# ESP-WRITE.net
KiCad netlist of a schematic drawn in EAGLE
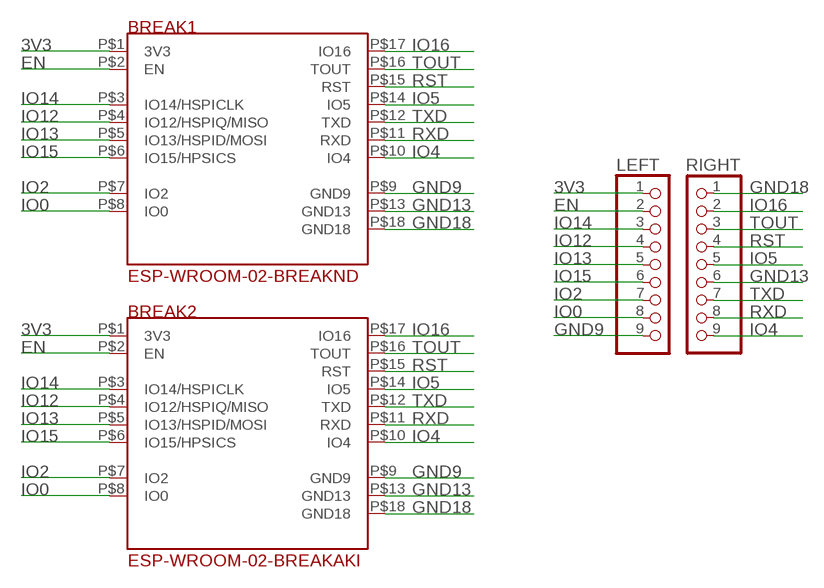
[diagram p0: schematic, sheet 1]

(export (version "E")
  (design (tool "Eeschema 10.0.6"))
  (components
    (comp (ref "BREAK1")
      (value "ESP-WROOM-02-BREAKND")
      (footprint "eagle-import:ESP-WROOM-02-BREAK-NODETAIL")
      (libsource (lib "eagle-import") (part "ESP-WROOM-02-BREAKND"))
    )
    (comp (ref "BREAK2")
      (value "ESP-WROOM-02-BREAKAKI")
      (footprint "eagle-import:ESP-WROOM-02-AKI")
      (libsource (lib "eagle-import") (part "ESP-WROOM-02-BREAKAKI"))
    )
    (comp (ref "LEFT")
      (value "PINHD-1X9")
      (footprint "eagle-import:1X09")
      (libsource (lib "eagle-import") (part "PINHD-1X9"))
    )
    (comp (ref "RIGHT")
      (value "PINHD-1X9")
      (footprint "eagle-import:1X09")
      (libsource (lib "eagle-import") (part "PINHD-1X9"))
    )
  )
  (nets
    (net (code "1") (name "/3V3") (class "Default")
      (node (ref "BREAK1") (pin "P$1") (pinfunction "3V3_P$1") (pintype "bidirectional"))
      (node (ref "BREAK2") (pin "P$1") (pinfunction "3V3_P$1") (pintype "bidirectional"))
      (node (ref "LEFT") (pin "1") (pinfunction "1_1") (pintype "passive"))
    )
    (net (code "2") (name "/EN") (class "Default")
      (node (ref "BREAK1") (pin "P$2") (pinfunction "EN_P$2") (pintype "bidirectional"))
      (node (ref "BREAK2") (pin "P$2") (pinfunction "EN_P$2") (pintype "bidirectional"))
      (node (ref "LEFT") (pin "2") (pinfunction "2_2") (pintype "passive"))
    )
    (net (code "3") (name "/GND9") (class "Default")
      (node (ref "BREAK1") (pin "P$9") (pinfunction "GND9_P$9") (pintype "bidirectional"))
      (node (ref "BREAK2") (pin "P$9") (pinfunction "GND9_P$9") (pintype "bidirectional"))
      (node (ref "LEFT") (pin "9") (pinfunction "9_9") (pintype "passive"))
    )
    (net (code "4") (name "/GND13") (class "Default")
      (node (ref "BREAK1") (pin "P$13") (pinfunction "GND13_P$13") (pintype "bidirectional"))
      (node (ref "BREAK2") (pin "P$13") (pinfunction "GND13_P$13") (pintype "bidirectional"))
      (node (ref "RIGHT") (pin "6") (pinfunction "6_6") (pintype "passive"))
    )
    (net (code "5") (name "/GND18") (class "Default")
      (node (ref "BREAK1") (pin "P$18") (pinfunction "GND18_P$18") (pintype "bidirectional"))
      (node (ref "BREAK2") (pin "P$18") (pinfunction "GND18_P$18") (pintype "bidirectional"))
      (node (ref "RIGHT") (pin "1") (pinfunction "1_1") (pintype "passive"))
    )
    (net (code "6") (name "/IO0") (class "Default")
      (node (ref "BREAK1") (pin "P$8") (pinfunction "IO0_P$8") (pintype "bidirectional"))
      (node (ref "BREAK2") (pin "P$8") (pinfunction "IO0_P$8") (pintype "bidirectional"))
      (node (ref "LEFT") (pin "8") (pinfunction "8_8") (pintype "passive"))
    )
    (net (code "7") (name "/IO2") (class "Default")
      (node (ref "BREAK1") (pin "P$7") (pinfunction "IO2_P$7") (pintype "bidirectional"))
      (node (ref "BREAK2") (pin "P$7") (pinfunction "IO2_P$7") (pintype "bidirectional"))
      (node (ref "LEFT") (pin "7") (pinfunction "7_7") (pintype "passive"))
    )
    (net (code "8") (name "/IO4") (class "Default")
      (node (ref "BREAK1") (pin "P$10") (pinfunction "IO4_P$10") (pintype "bidirectional"))
      (node (ref "BREAK2") (pin "P$10") (pinfunction "IO4_P$10") (pintype "bidirectional"))
      (node (ref "RIGHT") (pin "9") (pinfunction "9_9") (pintype "passive"))
    )
    (net (code "9") (name "/IO5") (class "Default")
      (node (ref "BREAK1") (pin "P$14") (pinfunction "IO5_P$14") (pintype "bidirectional"))
      (node (ref "BREAK2") (pin "P$14") (pinfunction "IO5_P$14") (pintype "bidirectional"))
      (node (ref "RIGHT") (pin "5") (pinfunction "5_5") (pintype "passive"))
    )
    (net (code "10") (name "/IO12") (class "Default")
      (node (ref "BREAK1") (pin "P$4") (pinfunction "IO12/HSPIQ/MISO_P$4") (pintype "bidirectional"))
      (node (ref "BREAK2") (pin "P$4") (pinfunction "IO12/HSPIQ/MISO_P$4") (pintype "bidirectional"))
      (node (ref "LEFT") (pin "4") (pinfunction "4_4") (pintype "passive"))
    )
    (net (code "11") (name "/IO13") (class "Default")
      (node (ref "BREAK1") (pin "P$5") (pinfunction "IO13/HSPID/MOSI_P$5") (pintype "bidirectional"))
      (node (ref "BREAK2") (pin "P$5") (pinfunction "IO13/HSPID/MOSI_P$5") (pintype "bidirectional"))
      (node (ref "LEFT") (pin "5") (pinfunction "5_5") (pintype "passive"))
    )
    (net (code "12") (name "/IO14") (class "Default")
      (node (ref "BREAK1") (pin "P$3") (pinfunction "IO14/HSPICLK_P$3") (pintype "bidirectional"))
      (node (ref "BREAK2") (pin "P$3") (pinfunction "IO14/HSPICLK_P$3") (pintype "bidirectional"))
      (node (ref "LEFT") (pin "3") (pinfunction "3_3") (pintype "passive"))
    )
    (net (code "13") (name "/IO15") (class "Default")
      (node (ref "BREAK1") (pin "P$6") (pinfunction "IO15/HPSICS_P$6") (pintype "bidirectional"))
      (node (ref "BREAK2") (pin "P$6") (pinfunction "IO15/HPSICS_P$6") (pintype "bidirectional"))
      (node (ref "LEFT") (pin "6") (pinfunction "6_6") (pintype "passive"))
    )
    (net (code "14") (name "/IO16") (class "Default")
      (node (ref "BREAK1") (pin "P$17") (pinfunction "IO16_P$17") (pintype "bidirectional"))
      (node (ref "BREAK2") (pin "P$17") (pinfunction "IO16_P$17") (pintype "bidirectional"))
      (node (ref "RIGHT") (pin "2") (pinfunction "2_2") (pintype "passive"))
    )
    (net (code "15") (name "/RST") (class "Default")
      (node (ref "BREAK1") (pin "P$15") (pinfunction "RST_P$15") (pintype "bidirectional"))
      (node (ref "BREAK2") (pin "P$15") (pinfunction "RST_P$15") (pintype "bidirectional"))
      (node (ref "RIGHT") (pin "4") (pinfunction "4_4") (pintype "passive"))
    )
    (net (code "16") (name "/RXD") (class "Default")
      (node (ref "BREAK1") (pin "P$11") (pinfunction "RXD_P$11") (pintype "bidirectional"))
      (node (ref "BREAK2") (pin "P$11") (pinfunction "RXD_P$11") (pintype "bidirectional"))
      (node (ref "RIGHT") (pin "8") (pinfunction "8_8") (pintype "passive"))
    )
    (net (code "17") (name "/TOUT") (class "Default")
      (node (ref "BREAK1") (pin "P$16") (pinfunction "TOUT_P$16") (pintype "bidirectional"))
      (node (ref "BREAK2") (pin "P$16") (pinfunction "TOUT_P$16") (pintype "bidirectional"))
      (node (ref "RIGHT") (pin "3") (pinfunction "3_3") (pintype "passive"))
    )
    (net (code "18") (name "/TXD") (class "Default")
      (node (ref "BREAK1") (pin "P$12") (pinfunction "TXD_P$12") (pintype "bidirectional"))
      (node (ref "BREAK2") (pin "P$12") (pinfunction "TXD_P$12") (pintype "bidirectional"))
      (node (ref "RIGHT") (pin "7") (pinfunction "7_7") (pintype "passive"))
    )
  )
)
